# gbit-poe-splitter.net
KiCad netlist of a schematic drawn in EAGLE
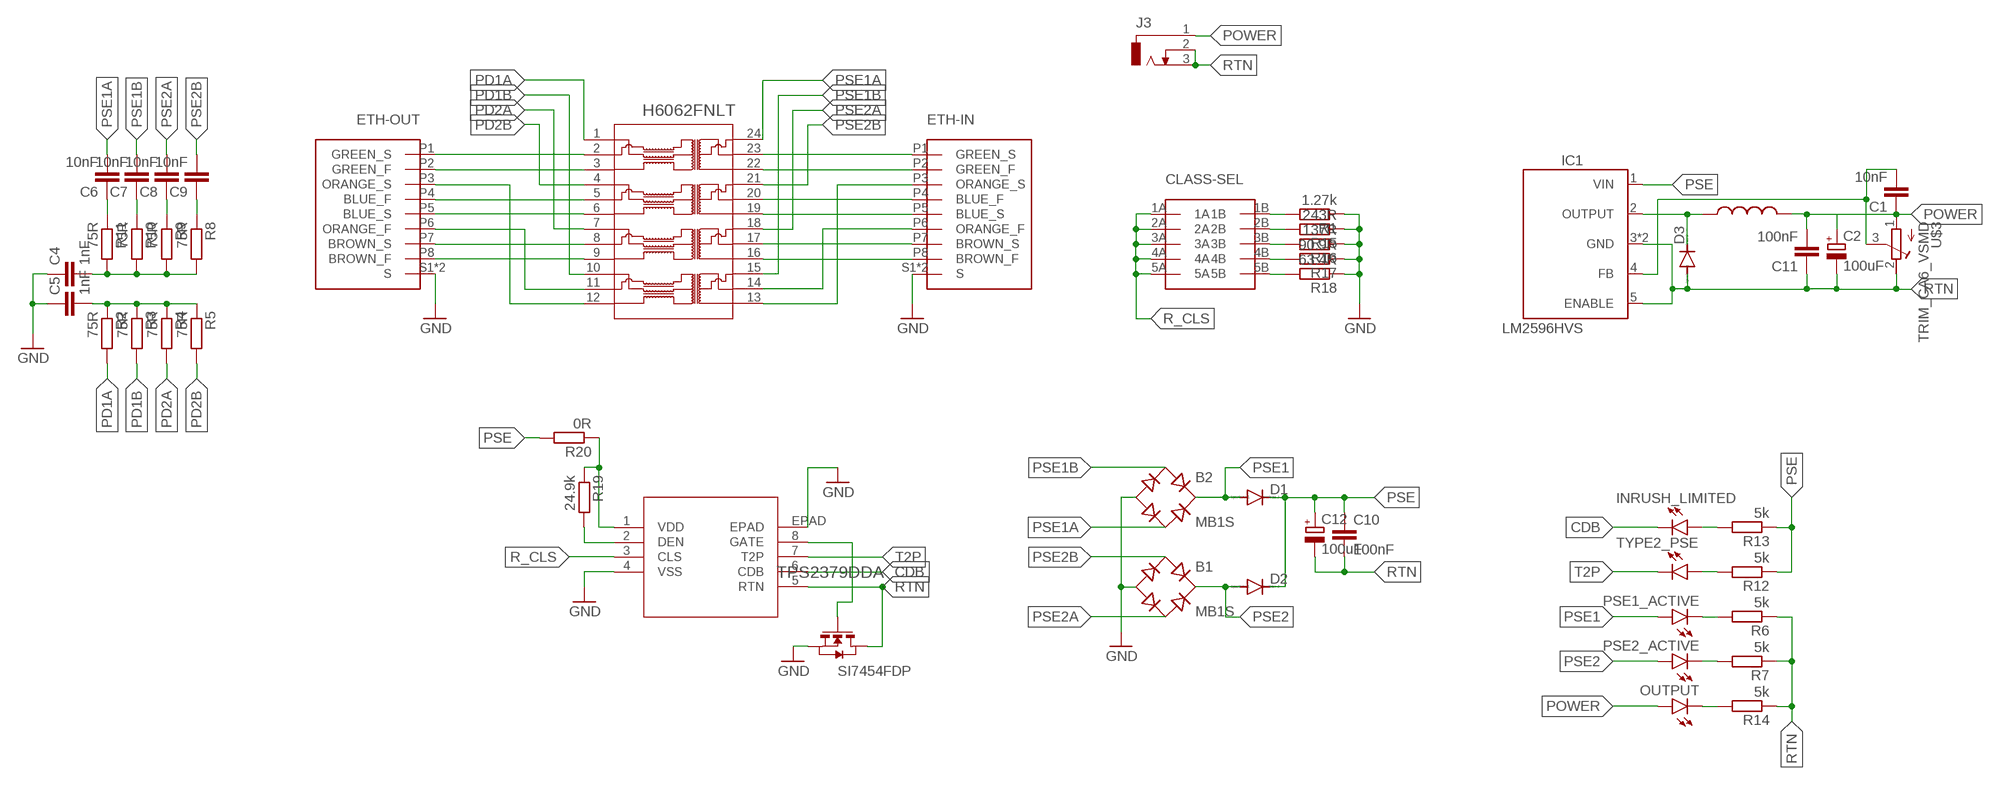
[diagram p0: schematic, sheet 1]

(export (version "E")
  (design (tool "Eeschema 10.0.6"))
  (components
    (comp (ref "B1")
      (value "MB1S")
      (footprint "eagle-import:SOIC-4")
      (libsource (lib "eagle-import") (part "MBS1"))
    )
    (comp (ref "B2")
      (value "MB1S")
      (footprint "eagle-import:SOIC-4")
      (libsource (lib "eagle-import") (part "MBS1"))
    )
    (comp (ref "C1")
      (value "10nF")
      (footprint "eagle-import:C0603K")
      (libsource (lib "eagle-import") (part "C-EUC0603K"))
    )
    (comp (ref "C2")
      (value "100uF")
      (footprint "eagle-import:153CLV-1012")
      (libsource (lib "eagle-import") (part "CPOL-EU153CLV-1012"))
    )
    (comp (ref "C4")
      (value "1nF")
      (footprint "eagle-import:C0603K")
      (libsource (lib "eagle-import") (part "C-EUC0603K"))
    )
    (comp (ref "C5")
      (value "1nF")
      (footprint "eagle-import:C0603K")
      (libsource (lib "eagle-import") (part "C-EUC0603K"))
    )
    (comp (ref "C6")
      (value "10nF")
      (footprint "eagle-import:C0603K")
      (libsource (lib "eagle-import") (part "C-EUC0603K"))
    )
    (comp (ref "C7")
      (value "10nF")
      (footprint "eagle-import:C0603K")
      (libsource (lib "eagle-import") (part "C-EUC0603K"))
    )
    (comp (ref "C8")
      (value "10nF")
      (footprint "eagle-import:C0603K")
      (libsource (lib "eagle-import") (part "C-EUC0603K"))
    )
    (comp (ref "C9")
      (value "10nF")
      (footprint "eagle-import:C0603K")
      (libsource (lib "eagle-import") (part "C-EUC0603K"))
    )
    (comp (ref "C10")
      (value "100nF")
      (footprint "eagle-import:C0805")
      (libsource (lib "eagle-import") (part "C-EUC0805"))
    )
    (comp (ref "C11")
      (value "100nF")
      (footprint "eagle-import:C0805")
      (libsource (lib "eagle-import") (part "C-EUC0805"))
    )
    (comp (ref "C12")
      (value "100uF")
      (footprint "eagle-import:153CLV-1012")
      (libsource (lib "eagle-import") (part "CPOL-EU153CLV-1012"))
    )
    (comp (ref "CLASS-SEL")
      (value "54202-T0803AB01LF")
      (footprint "eagle-import:54202-T0803AB01LF")
      (libsource (lib "eagle-import") (part "54202-T0803AB01LF"))
    )
    (comp (ref "D1")
      (value "DIODE-DO-214AC")
      (footprint "eagle-import:DO-214AC")
      (libsource (lib "eagle-import") (part "DIODE-DO-214AC"))
    )
    (comp (ref "D2")
      (value "DIODE-DO-214AC")
      (footprint "eagle-import:DO-214AC")
      (libsource (lib "eagle-import") (part "DIODE-DO-214AC"))
    )
    (comp (ref "D3")
      (value "DIODE-DO-214AC")
      (footprint "eagle-import:DO-214AC")
      (libsource (lib "eagle-import") (part "DIODE-DO-214AC"))
    )
    (comp (ref "ETH-IN")
      (value "RJLSE-4X1XX-01")
      (footprint "eagle-import:RJLSE-4X1XX-01")
      (libsource (lib "eagle-import") (part "RJLSE-4X1XX-01"))
    )
    (comp (ref "ETH-OUT")
      (value "RJLSE-4X1XX-01")
      (footprint "eagle-import:RJLSE-4X1XX-01")
      (libsource (lib "eagle-import") (part "RJLSE-4X1XX-01"))
    )
    (comp (ref "IC1")
      (value "LM2596HVS")
      (footprint "eagle-import:TO263-5")
      (libsource (lib "eagle-import") (part "LM2596HVS"))
    )
    (comp (ref "INRUSH_LIMITED")
      (value "LEDCHIPLED_0603")
      (footprint "eagle-import:CHIPLED_0603")
      (libsource (lib "eagle-import") (part "LEDCHIPLED_0603"))
    )
    (comp (ref "J3")
      (value "DCJ0303")
      (footprint "eagle-import:DCJ0303")
      (libsource (lib "eagle-import") (part "DCJ0303"))
    )
    (comp (ref "OUTPUT")
      (value "LEDCHIPLED_0603")
      (footprint "eagle-import:CHIPLED_0603")
      (libsource (lib "eagle-import") (part "LEDCHIPLED_0603"))
    )
    (comp (ref "PSE1_ACTIVE")
      (value "LEDCHIPLED_0603")
      (footprint "eagle-import:CHIPLED_0603")
      (libsource (lib "eagle-import") (part "LEDCHIPLED_0603"))
    )
    (comp (ref "PSE2_ACTIVE")
      (value "LEDCHIPLED_0603")
      (footprint "eagle-import:CHIPLED_0603")
      (libsource (lib "eagle-import") (part "LEDCHIPLED_0603"))
    )
    (comp (ref "R1")
      (value "1.27k")
      (footprint "eagle-import:R0603")
      (libsource (lib "eagle-import") (part "R-EU_R0603"))
    )
    (comp (ref "R2")
      (value "75R")
      (footprint "eagle-import:R0603")
      (libsource (lib "eagle-import") (part "R-EU_R0603"))
    )
    (comp (ref "R3")
      (value "75R")
      (footprint "eagle-import:R0603")
      (libsource (lib "eagle-import") (part "R-EU_R0603"))
    )
    (comp (ref "R4")
      (value "75R")
      (footprint "eagle-import:R0603")
      (libsource (lib "eagle-import") (part "R-EU_R0603"))
    )
    (comp (ref "R5")
      (value "75R")
      (footprint "eagle-import:R0603")
      (libsource (lib "eagle-import") (part "R-EU_R0603"))
    )
    (comp (ref "R6")
      (value "5k")
      (footprint "eagle-import:R0603")
      (libsource (lib "eagle-import") (part "R-EU_R0603"))
    )
    (comp (ref "R7")
      (value "5k")
      (footprint "eagle-import:R0603")
      (libsource (lib "eagle-import") (part "R-EU_R0603"))
    )
    (comp (ref "R8")
      (value "75R")
      (footprint "eagle-import:R0603")
      (libsource (lib "eagle-import") (part "R-EU_R0603"))
    )
    (comp (ref "R9")
      (value "75R")
      (footprint "eagle-import:R0603")
      (libsource (lib "eagle-import") (part "R-EU_R0603"))
    )
    (comp (ref "R10")
      (value "75R")
      (footprint "eagle-import:R0603")
      (libsource (lib "eagle-import") (part "R-EU_R0603"))
    )
    (comp (ref "R11")
      (value "75R")
      (footprint "eagle-import:R0603")
      (libsource (lib "eagle-import") (part "R-EU_R0603"))
    )
    (comp (ref "R12")
      (value "5k")
      (footprint "eagle-import:R0603")
      (libsource (lib "eagle-import") (part "R-EU_R0603"))
    )
    (comp (ref "R13")
      (value "5k")
      (footprint "eagle-import:R0603")
      (libsource (lib "eagle-import") (part "R-EU_R0603"))
    )
    (comp (ref "R14")
      (value "5k")
      (footprint "eagle-import:R0603")
      (libsource (lib "eagle-import") (part "R-EU_R0603"))
    )
    (comp (ref "R15")
      (value "243R")
      (footprint "eagle-import:R0603")
      (libsource (lib "eagle-import") (part "R-EU_R0603"))
    )
    (comp (ref "R16")
      (value "137R")
      (footprint "eagle-import:R0603")
      (libsource (lib "eagle-import") (part "R-EU_R0603"))
    )
    (comp (ref "R17")
      (value "90.9R")
      (footprint "eagle-import:R0603")
      (libsource (lib "eagle-import") (part "R-EU_R0603"))
    )
    (comp (ref "R18")
      (value "63.4R")
      (footprint "eagle-import:R0603")
      (libsource (lib "eagle-import") (part "R-EU_R0603"))
    )
    (comp (ref "R19")
      (value "24.9k")
      (footprint "eagle-import:R0603")
      (libsource (lib "eagle-import") (part "R-EU_R0603"))
    )
    (comp (ref "R20")
      (value "0R")
      (footprint "eagle-import:R1206")
      (libsource (lib "eagle-import") (part "R-EU_R1206"))
    )
    (comp (ref "TYPE2_PSE")
      (value "LEDCHIPLED_0603")
      (footprint "eagle-import:CHIPLED_0603")
      (libsource (lib "eagle-import") (part "LEDCHIPLED_0603"))
    )
    (comp (ref "U$1")
      (value "SI7454FDP")
      (footprint "eagle-import:POWERPAK-SO-8")
      (libsource (lib "eagle-import") (part "SI7454FDP"))
    )
    (comp (ref "U$2")
      (value "INDUCTOR-SMD7070")
      (footprint "eagle-import:INDUCTOR-SMD")
      (libsource (lib "eagle-import") (part "INDUCTOR-SMD7070"))
    )
    (comp (ref "U$3")
      (value "TRIM_CA6_VSMD")
      (footprint "eagle-import:TRIM_CA6_VSMD")
      (libsource (lib "eagle-import") (part "TRIM_CA6_VSMD"))
    )
    (comp (ref "U1")
      (value "TPS2379DDA")
      (footprint "eagle-import:DDA8_3P1X2P4_TEX")
      (fields (field (name "COPYRIGHT") "Copyright (C) 2021 Ultra Librarian. All rights reserved."))
      (libsource (lib "eagle-import") (part "TPS2379DDA"))
    )
    (comp (ref "XMER1")
      (value "H6062FNLT")
      (footprint "eagle-import:H6062FNLT_PUL")
      (fields (field (name "COPYRIGHT") "Copyright (C) 2021 Ultra Librarian. All rights reserved."))
      (libsource (lib "eagle-import") (part "H6062FNLT"))
    )
  )
  (nets
    (net (code "1") (name "CDB") (class "Default")
      (node (ref "INRUSH_LIMITED") (pin "C") (pinfunction "C_C") (pintype "passive"))
      (node (ref "U1") (pin "6") (pinfunction "CDB_6") (pintype "output"))
    )
    (net (code "2") (name "GND") (class "Default")
      (node (ref "B1") (pin "-") (pinfunction "-_-") (pintype "passive"))
      (node (ref "B2") (pin "-") (pinfunction "-_-") (pintype "passive"))
      (node (ref "C4") (pin "1") (pinfunction "1_1") (pintype "passive"))
      (node (ref "C5") (pin "1") (pinfunction "1_1") (pintype "passive"))
      (node (ref "ETH-IN") (pin "S1") (pinfunction "S_S1") (pintype "bidirectional"))
      (node (ref "ETH-IN") (pin "S2") (pinfunction "S_S2") (pintype "bidirectional"))
      (node (ref "ETH-OUT") (pin "S1") (pinfunction "S_S1") (pintype "bidirectional"))
      (node (ref "ETH-OUT") (pin "S2") (pinfunction "S_S2") (pintype "bidirectional"))
      (node (ref "R1") (pin "1") (pinfunction "1_1") (pintype "passive"))
      (node (ref "R15") (pin "1") (pinfunction "1_1") (pintype "passive"))
      (node (ref "R16") (pin "1") (pinfunction "1_1") (pintype "passive"))
      (node (ref "R17") (pin "1") (pinfunction "1_1") (pintype "passive"))
      (node (ref "R18") (pin "1") (pinfunction "1_1") (pintype "passive"))
      (node (ref "U$1") (pin "S1") (pinfunction "S_S1") (pintype "passive"))
      (node (ref "U$1") (pin "S2") (pinfunction "S_S2") (pintype "passive"))
      (node (ref "U$1") (pin "S3") (pinfunction "S_S3") (pintype "passive"))
      (node (ref "U1") (pin "4") (pinfunction "VSS_4") (pintype "power_in"))
      (node (ref "U1") (pin "EPAD") (pinfunction "EPAD_EPAD") (pintype "passive"))
    )
    (net (code "3") (name "Net-(C4-Pad2)") (class "Default")
      (node (ref "C4") (pin "2") (pinfunction "2_2") (pintype "passive"))
      (node (ref "R10") (pin "2") (pinfunction "2_2") (pintype "passive"))
      (node (ref "R11") (pin "2") (pinfunction "2_2") (pintype "passive"))
      (node (ref "R8") (pin "2") (pinfunction "2_2") (pintype "passive"))
      (node (ref "R9") (pin "2") (pinfunction "2_2") (pintype "passive"))
    )
    (net (code "4") (name "Net-(C5-Pad2)") (class "Default")
      (node (ref "C5") (pin "2") (pinfunction "2_2") (pintype "passive"))
      (node (ref "R2") (pin "1") (pinfunction "1_1") (pintype "passive"))
      (node (ref "R3") (pin "1") (pinfunction "1_1") (pintype "passive"))
      (node (ref "R4") (pin "1") (pinfunction "1_1") (pintype "passive"))
      (node (ref "R5") (pin "1") (pinfunction "1_1") (pintype "passive"))
    )
    (net (code "5") (name "Net-(C6-Pad1)") (class "Default")
      (node (ref "C6") (pin "1") (pinfunction "1_1") (pintype "passive"))
      (node (ref "R11") (pin "1") (pinfunction "1_1") (pintype "passive"))
    )
    (net (code "6") (name "Net-(C7-Pad1)") (class "Default")
      (node (ref "C7") (pin "1") (pinfunction "1_1") (pintype "passive"))
      (node (ref "R10") (pin "1") (pinfunction "1_1") (pintype "passive"))
    )
    (net (code "7") (name "Net-(C8-Pad1)") (class "Default")
      (node (ref "C8") (pin "1") (pinfunction "1_1") (pintype "passive"))
      (node (ref "R9") (pin "1") (pinfunction "1_1") (pintype "passive"))
    )
    (net (code "8") (name "Net-(C9-Pad1)") (class "Default")
      (node (ref "C9") (pin "1") (pinfunction "1_1") (pintype "passive"))
      (node (ref "R8") (pin "1") (pinfunction "1_1") (pintype "passive"))
    )
    (net (code "9") (name "Net-(CLASS-SEL-Pad1B)") (class "Default")
      (node (ref "CLASS-SEL") (pin "1B") (pinfunction "1B_1B") (pintype "bidirectional"))
      (node (ref "R1") (pin "2") (pinfunction "2_2") (pintype "passive"))
    )
    (net (code "10") (name "Net-(CLASS-SEL-Pad2B)") (class "Default")
      (node (ref "CLASS-SEL") (pin "2B") (pinfunction "2B_2B") (pintype "bidirectional"))
      (node (ref "R15") (pin "2") (pinfunction "2_2") (pintype "passive"))
    )
    (net (code "11") (name "Net-(CLASS-SEL-Pad3B)") (class "Default")
      (node (ref "CLASS-SEL") (pin "3B") (pinfunction "3B_3B") (pintype "bidirectional"))
      (node (ref "R16") (pin "2") (pinfunction "2_2") (pintype "passive"))
    )
    (net (code "12") (name "Net-(CLASS-SEL-Pad4B)") (class "Default")
      (node (ref "CLASS-SEL") (pin "4B") (pinfunction "4B_4B") (pintype "bidirectional"))
      (node (ref "R17") (pin "2") (pinfunction "2_2") (pintype "passive"))
    )
    (net (code "13") (name "Net-(CLASS-SEL-Pad5B)") (class "Default")
      (node (ref "CLASS-SEL") (pin "5B") (pinfunction "5B_5B") (pintype "bidirectional"))
      (node (ref "R18") (pin "2") (pinfunction "2_2") (pintype "passive"))
    )
    (net (code "14") (name "Net-(ETH-IN-BLUE_F)") (class "Default")
      (node (ref "ETH-IN") (pin "P4") (pinfunction "BLUE_F_P4") (pintype "bidirectional"))
      (node (ref "XMER1") (pin "20") (pinfunction "20_20") (pintype "passive"))
    )
    (net (code "15") (name "Net-(ETH-IN-BLUE_S)") (class "Default")
      (node (ref "ETH-IN") (pin "P5") (pinfunction "BLUE_S_P5") (pintype "bidirectional"))
      (node (ref "XMER1") (pin "19") (pinfunction "19_19") (pintype "passive"))
    )
    (net (code "16") (name "Net-(ETH-IN-BROWN_F)") (class "Default")
      (node (ref "ETH-IN") (pin "P8") (pinfunction "BROWN_F_P8") (pintype "bidirectional"))
      (node (ref "XMER1") (pin "16") (pinfunction "16_16") (pintype "passive"))
    )
    (net (code "17") (name "Net-(ETH-IN-BROWN_S)") (class "Default")
      (node (ref "ETH-IN") (pin "P7") (pinfunction "BROWN_S_P7") (pintype "bidirectional"))
      (node (ref "XMER1") (pin "17") (pinfunction "17_17") (pintype "passive"))
    )
    (net (code "18") (name "Net-(ETH-IN-GREEN_F)") (class "Default")
      (node (ref "ETH-IN") (pin "P2") (pinfunction "GREEN_F_P2") (pintype "bidirectional"))
      (node (ref "XMER1") (pin "22") (pinfunction "22_22") (pintype "passive"))
    )
    (net (code "19") (name "Net-(ETH-IN-GREEN_S)") (class "Default")
      (node (ref "ETH-IN") (pin "P1") (pinfunction "GREEN_S_P1") (pintype "bidirectional"))
      (node (ref "XMER1") (pin "23") (pinfunction "23_23") (pintype "passive"))
    )
    (net (code "20") (name "Net-(ETH-IN-ORANGE_F)") (class "Default")
      (node (ref "ETH-IN") (pin "P6") (pinfunction "ORANGE_F_P6") (pintype "bidirectional"))
      (node (ref "XMER1") (pin "14") (pinfunction "14_14") (pintype "passive"))
    )
    (net (code "21") (name "Net-(ETH-IN-ORANGE_S)") (class "Default")
      (node (ref "ETH-IN") (pin "P3") (pinfunction "ORANGE_S_P3") (pintype "bidirectional"))
      (node (ref "XMER1") (pin "13") (pinfunction "13_13") (pintype "passive"))
    )
    (net (code "22") (name "Net-(ETH-OUT-BLUE_F)") (class "Default")
      (node (ref "ETH-OUT") (pin "P4") (pinfunction "BLUE_F_P4") (pintype "bidirectional"))
      (node (ref "XMER1") (pin "5") (pinfunction "5_5") (pintype "passive"))
    )
    (net (code "23") (name "Net-(ETH-OUT-BLUE_S)") (class "Default")
      (node (ref "ETH-OUT") (pin "P5") (pinfunction "BLUE_S_P5") (pintype "bidirectional"))
      (node (ref "XMER1") (pin "6") (pinfunction "6_6") (pintype "passive"))
    )
    (net (code "24") (name "Net-(ETH-OUT-BROWN_F)") (class "Default")
      (node (ref "ETH-OUT") (pin "P8") (pinfunction "BROWN_F_P8") (pintype "bidirectional"))
      (node (ref "XMER1") (pin "9") (pinfunction "9_9") (pintype "passive"))
    )
    (net (code "25") (name "Net-(ETH-OUT-BROWN_S)") (class "Default")
      (node (ref "ETH-OUT") (pin "P7") (pinfunction "BROWN_S_P7") (pintype "bidirectional"))
      (node (ref "XMER1") (pin "8") (pinfunction "8_8") (pintype "passive"))
    )
    (net (code "26") (name "Net-(ETH-OUT-GREEN_F)") (class "Default")
      (node (ref "ETH-OUT") (pin "P2") (pinfunction "GREEN_F_P2") (pintype "bidirectional"))
      (node (ref "XMER1") (pin "3") (pinfunction "3_3") (pintype "passive"))
    )
    (net (code "27") (name "Net-(ETH-OUT-GREEN_S)") (class "Default")
      (node (ref "ETH-OUT") (pin "P1") (pinfunction "GREEN_S_P1") (pintype "bidirectional"))
      (node (ref "XMER1") (pin "2") (pinfunction "2_2") (pintype "passive"))
    )
    (net (code "28") (name "Net-(ETH-OUT-ORANGE_F)") (class "Default")
      (node (ref "ETH-OUT") (pin "P6") (pinfunction "ORANGE_F_P6") (pintype "bidirectional"))
      (node (ref "XMER1") (pin "11") (pinfunction "11_11") (pintype "passive"))
    )
    (net (code "29") (name "Net-(ETH-OUT-ORANGE_S)") (class "Default")
      (node (ref "ETH-OUT") (pin "P3") (pinfunction "ORANGE_S_P3") (pintype "bidirectional"))
      (node (ref "XMER1") (pin "12") (pinfunction "12_12") (pintype "passive"))
    )
    (net (code "30") (name "Net-(IC1-FB)") (class "Default")
      (node (ref "C1") (pin "2") (pinfunction "2_2") (pintype "passive"))
      (node (ref "IC1") (pin "4") (pinfunction "FB_4") (pintype "input"))
      (node (ref "U$3") (pin "3") (pinfunction "S_3") (pintype "passive"))
    )
    (net (code "31") (name "Net-(IC1-OUTPUT)") (class "Default")
      (node (ref "D3") (pin "C") (pinfunction "C_C") (pintype "passive"))
      (node (ref "IC1") (pin "2") (pinfunction "OUTPUT_2") (pintype "power_in"))
      (node (ref "U$2") (pin "1") (pinfunction "1_1") (pintype "passive"))
    )
    (net (code "32") (name "Net-(INRUSH_LIMITED-PadA)") (class "Default")
      (node (ref "INRUSH_LIMITED") (pin "A") (pinfunction "A_A") (pintype "passive"))
      (node (ref "R13") (pin "2") (pinfunction "2_2") (pintype "passive"))
    )
    (net (code "33") (name "Net-(OUTPUT-PadC)") (class "Default")
      (node (ref "OUTPUT") (pin "C") (pinfunction "C_C") (pintype "passive"))
      (node (ref "R14") (pin "2") (pinfunction "2_2") (pintype "passive"))
    )
    (net (code "34") (name "Net-(PSE1_ACTIVE-PadC)") (class "Default")
      (node (ref "PSE1_ACTIVE") (pin "C") (pinfunction "C_C") (pintype "passive"))
      (node (ref "R6") (pin "2") (pinfunction "2_2") (pintype "passive"))
    )
    (net (code "35") (name "Net-(PSE2_ACTIVE-PadC)") (class "Default")
      (node (ref "PSE2_ACTIVE") (pin "C") (pinfunction "C_C") (pintype "passive"))
      (node (ref "R7") (pin "2") (pinfunction "2_2") (pintype "passive"))
    )
    (net (code "36") (name "Net-(R12-Pad2)") (class "Default")
      (node (ref "R12") (pin "2") (pinfunction "2_2") (pintype "passive"))
      (node (ref "TYPE2_PSE") (pin "A") (pinfunction "A_A") (pintype "passive"))
    )
    (net (code "37") (name "Net-(U1-DEN)") (class "Default")
      (node (ref "R19") (pin "2") (pinfunction "2_2") (pintype "passive"))
      (node (ref "U1") (pin "2") (pinfunction "DEN_2") (pintype "bidirectional"))
    )
    (net (code "38") (name "Net-(U1-GATE)") (class "Default")
      (node (ref "U$1") (pin "G") (pinfunction "G_G") (pintype "passive"))
      (node (ref "U1") (pin "8") (pinfunction "GATE_8") (pintype "output"))
    )
    (net (code "39") (name "Net-(U1-VDD)") (class "Default")
      (node (ref "R19") (pin "1") (pinfunction "1_1") (pintype "passive"))
      (node (ref "R20") (pin "1") (pinfunction "1_1") (pintype "passive"))
      (node (ref "U1") (pin "1") (pinfunction "VDD_1") (pintype "power_in"))
    )
    (net (code "40") (name "PD1A") (class "Default")
      (node (ref "R2") (pin "2") (pinfunction "2_2") (pintype "passive"))
      (node (ref "XMER1") (pin "1") (pinfunction "1_1") (pintype "passive"))
    )
    (net (code "41") (name "PD1B") (class "Default")
      (node (ref "R3") (pin "2") (pinfunction "2_2") (pintype "passive"))
      (node (ref "XMER1") (pin "10") (pinfunction "10_10") (pintype "passive"))
    )
    (net (code "42") (name "PD2A") (class "Default")
      (node (ref "R4") (pin "2") (pinfunction "2_2") (pintype "passive"))
      (node (ref "XMER1") (pin "7") (pinfunction "7_7") (pintype "passive"))
    )
    (net (code "43") (name "PD2B") (class "Default")
      (node (ref "R5") (pin "2") (pinfunction "2_2") (pintype "passive"))
      (node (ref "XMER1") (pin "4") (pinfunction "4_4") (pintype "passive"))
    )
    (net (code "44") (name "POWER") (class "Default")
      (node (ref "C1") (pin "1") (pinfunction "1_1") (pintype "passive"))
      (node (ref "C11") (pin "2") (pinfunction "2_2") (pintype "passive"))
      (node (ref "C2") (pin "+") (pinfunction "+_+") (pintype "passive"))
      (node (ref "J3") (pin "1") (pinfunction "1_1") (pintype "passive"))
      (node (ref "OUTPUT") (pin "A") (pinfunction "A_A") (pintype "passive"))
      (node (ref "U$2") (pin "2") (pinfunction "2_2") (pintype "passive"))
      (node (ref "U$3") (pin "1") (pinfunction "A_1") (pintype "passive"))
    )
    (net (code "45") (name "PSE") (class "Default")
      (node (ref "C10") (pin "1") (pinfunction "1_1") (pintype "passive"))
      (node (ref "C12") (pin "+") (pinfunction "+_+") (pintype "passive"))
      (node (ref "D1") (pin "C") (pinfunction "C_C") (pintype "passive"))
      (node (ref "D2") (pin "C") (pinfunction "C_C") (pintype "passive"))
      (node (ref "IC1") (pin "1") (pinfunction "VIN_1") (pintype "power_in"))
      (node (ref "R12") (pin "1") (pinfunction "1_1") (pintype "passive"))
      (node (ref "R13") (pin "1") (pinfunction "1_1") (pintype "passive"))
      (node (ref "R20") (pin "2") (pinfunction "2_2") (pintype "passive"))
    )
    (net (code "46") (name "PSE1") (class "Default")
      (node (ref "B2") (pin "+") (pinfunction "+_+") (pintype "passive"))
      (node (ref "D1") (pin "A") (pinfunction "A_A") (pintype "passive"))
      (node (ref "PSE1_ACTIVE") (pin "A") (pinfunction "A_A") (pintype "passive"))
    )
    (net (code "47") (name "PSE1A") (class "Default")
      (node (ref "B2") (pin "~2") (pinfunction "AC2_~2") (pintype "passive"))
      (node (ref "C6") (pin "2") (pinfunction "2_2") (pintype "passive"))
      (node (ref "XMER1") (pin "24") (pinfunction "24_24") (pintype "passive"))
    )
    (net (code "48") (name "PSE1B") (class "Default")
      (node (ref "B2") (pin "~1") (pinfunction "AC1_~1") (pintype "passive"))
      (node (ref "C7") (pin "2") (pinfunction "2_2") (pintype "passive"))
      (node (ref "XMER1") (pin "15") (pinfunction "15_15") (pintype "passive"))
    )
    (net (code "49") (name "PSE2") (class "Default")
      (node (ref "B1") (pin "+") (pinfunction "+_+") (pintype "passive"))
      (node (ref "D2") (pin "A") (pinfunction "A_A") (pintype "passive"))
      (node (ref "PSE2_ACTIVE") (pin "A") (pinfunction "A_A") (pintype "passive"))
    )
    (net (code "50") (name "PSE2A") (class "Default")
      (node (ref "B1") (pin "~2") (pinfunction "AC2_~2") (pintype "passive"))
      (node (ref "C8") (pin "2") (pinfunction "2_2") (pintype "passive"))
      (node (ref "XMER1") (pin "18") (pinfunction "18_18") (pintype "passive"))
    )
    (net (code "51") (name "PSE2B") (class "Default")
      (node (ref "B1") (pin "~1") (pinfunction "AC1_~1") (pintype "passive"))
      (node (ref "C9") (pin "2") (pinfunction "2_2") (pintype "passive"))
      (node (ref "XMER1") (pin "21") (pinfunction "21_21") (pintype "passive"))
    )
    (net (code "52") (name "RTN") (class "Default")
      (node (ref "C10") (pin "2") (pinfunction "2_2") (pintype "passive"))
      (node (ref "C11") (pin "1") (pinfunction "1_1") (pintype "passive"))
      (node (ref "C12") (pin "-") (pinfunction "-_-") (pintype "passive"))
      (node (ref "C2") (pin "-") (pinfunction "-_-") (pintype "passive"))
      (node (ref "D3") (pin "A") (pinfunction "A_A") (pintype "passive"))
      (node (ref "IC1") (pin "3") (pinfunction "GND_3") (pintype "power_in"))
      (node (ref "IC1") (pin "5") (pinfunction "ENABLE_5") (pintype "input"))
      (node (ref "IC1") (pin "6") (pinfunction "GND_6") (pintype "power_in"))
      (node (ref "J3") (pin "2") (pinfunction "2_2") (pintype "passive"))
      (node (ref "J3") (pin "3") (pinfunction "3_3") (pintype "passive"))
      (node (ref "R14") (pin "1") (pinfunction "1_1") (pintype "passive"))
      (node (ref "R6") (pin "1") (pinfunction "1_1") (pintype "passive"))
      (node (ref "R7") (pin "1") (pinfunction "1_1") (pintype "passive"))
      (node (ref "U$1") (pin "D1") (pinfunction "D_D1") (pintype "passive"))
      (node (ref "U$1") (pin "D2") (pinfunction "D_D2") (pintype "passive"))
      (node (ref "U$1") (pin "D3") (pinfunction "D_D3") (pintype "passive"))
      (node (ref "U$1") (pin "D4") (pinfunction "D_D4") (pintype "passive"))
      (node (ref "U$1") (pin "DPAD") (pinfunction "D_DPAD") (pintype "passive"))
      (node (ref "U$3") (pin "2") (pinfunction "E_2") (pintype "passive"))
      (node (ref "U1") (pin "5") (pinfunction "RTN_5") (pintype "passive"))
    )
    (net (code "53") (name "R_CLS") (class "Default")
      (node (ref "CLASS-SEL") (pin "1A") (pinfunction "1A_1A") (pintype "bidirectional"))
      (node (ref "CLASS-SEL") (pin "2A") (pinfunction "2A_2A") (pintype "bidirectional"))
      (node (ref "CLASS-SEL") (pin "3A") (pinfunction "3A_3A") (pintype "bidirectional"))
      (node (ref "CLASS-SEL") (pin "4A") (pinfunction "4A_4A") (pintype "bidirectional"))
      (node (ref "CLASS-SEL") (pin "5A") (pinfunction "5A_5A") (pintype "bidirectional"))
      (node (ref "U1") (pin "3") (pinfunction "CLS_3") (pintype "output"))
    )
    (net (code "54") (name "T2P") (class "Default")
      (node (ref "TYPE2_PSE") (pin "C") (pinfunction "C_C") (pintype "passive"))
      (node (ref "U1") (pin "7") (pinfunction "T2P_7") (pintype "output"))
    )
  )
)
